# Sheet1.net
KiCad netlist of a schematic drawn in Altium Designer
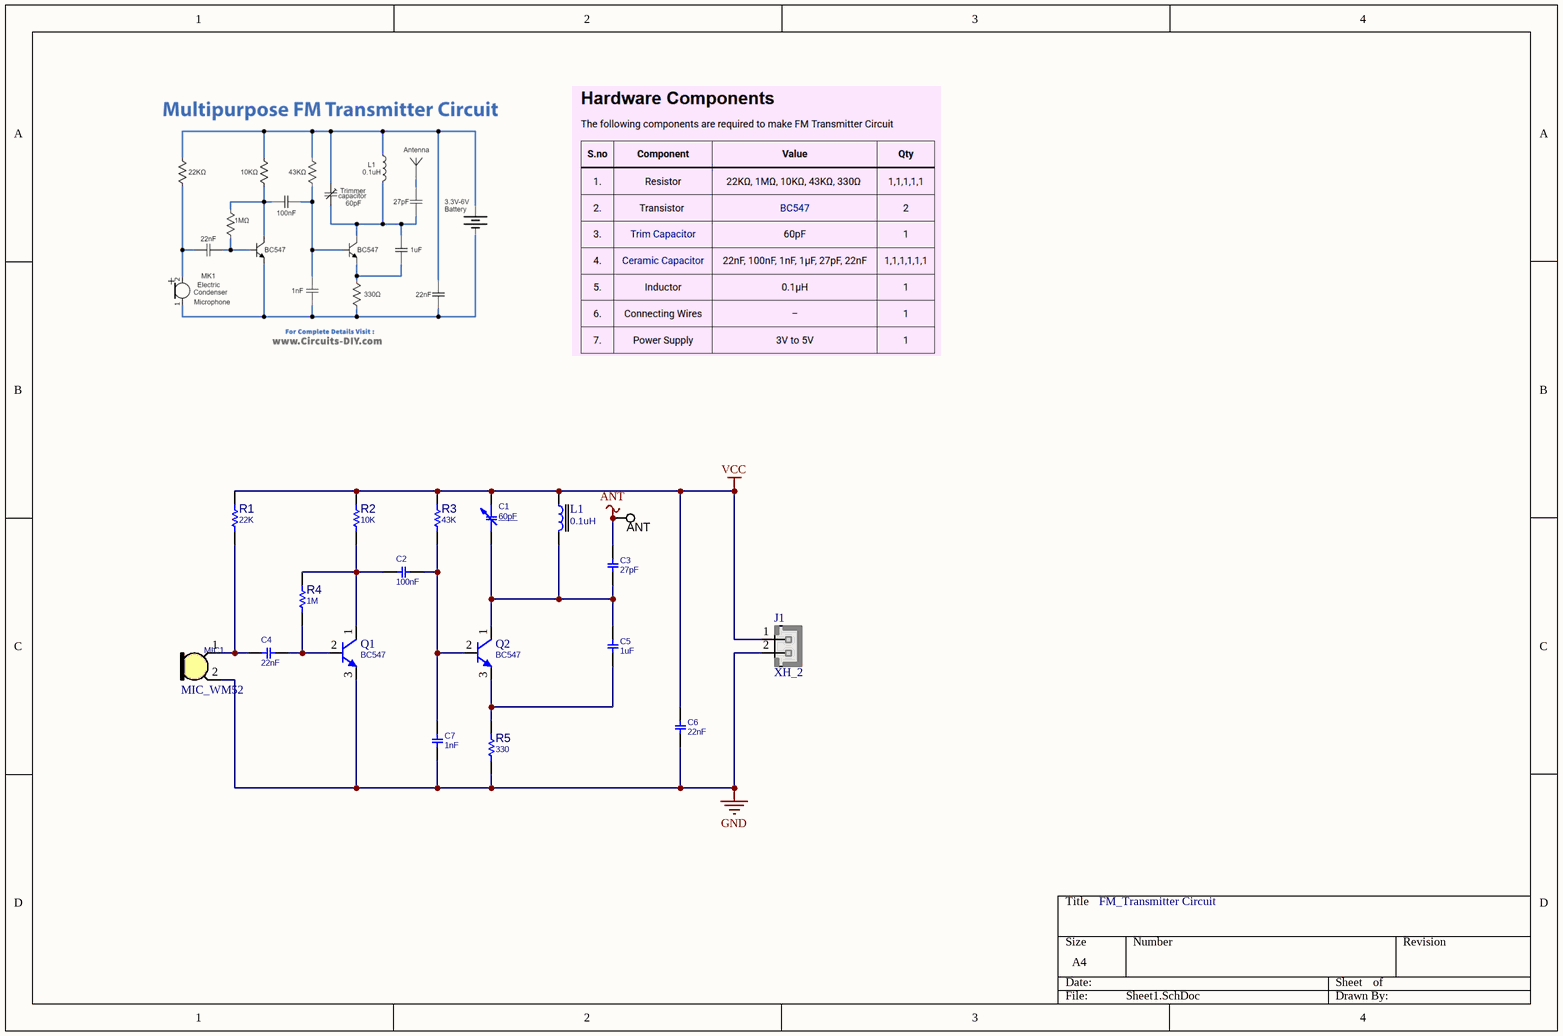
[diagram p0: Sheet1.SchDoc]

(export (version "E")
  (design (tool "Eeschema 10.0.6"))
  (components
    (comp (ref "ANT")
      (value "TESTPOINT_PROBE")
      (footprint "TP80D50")
      (description "TEST POINT")
      (fields (field (name "MANF") "MANF") (field (name "MANF_P#") "MANF_P#"))
      (libsource (lib "test-tp_jumper") (part "TESTPOINT_PROBE"))
    )
    (comp (ref "C1")
      (value "60pF")
      (footprint "CTRM_6X6")
      (description "CAP, THD, TRIMMER")
      (fields (field (name "MANF_P#") "MANF_PART#") (field (name "MANF") "MANF"))
      (libsource (lib "passive_thd") (part "CAP_THD_TRIMMER"))
    )
    (comp (ref "C2")
      (value "100nF")
      (footprint "C_CER_D5")
      (description "CAP, THD, CER MULTI LAYER,")
      (fields (field (name "MANF_P#") "MANF_PART#") (field (name "MANF") "MANF"))
      (libsource (lib "passive_thd") (part "CAP_THD_CER"))
    )
    (comp (ref "C3")
      (value "27pF")
      (footprint "C_CER_D5")
      (description "CAP, THD, CER MULTI LAYER,")
      (fields (field (name "MANF_P#") "MANF_PART#") (field (name "MANF") "MANF"))
      (libsource (lib "passive_thd") (part "CAP_THD_CER"))
    )
    (comp (ref "C4")
      (value "22nF")
      (footprint "C_CER_D5")
      (description "CAP, THD, CER MULTI LAYER,")
      (fields (field (name "MANF_P#") "MANF_PART#") (field (name "MANF") "MANF"))
      (libsource (lib "passive_thd") (part "CAP_THD_CER"))
    )
    (comp (ref "C5")
      (value "1uF")
      (footprint "C_CER_D5")
      (description "CAP, THD, CER MULTI LAYER,")
      (fields (field (name "MANF_P#") "MANF_PART#") (field (name "MANF") "MANF"))
      (libsource (lib "passive_thd") (part "CAP_THD_CER"))
    )
    (comp (ref "C6")
      (value "22nF")
      (footprint "C_CER_D5")
      (description "CAP, THD, CER MULTI LAYER,")
      (fields (field (name "MANF_P#") "MANF_PART#") (field (name "MANF") "MANF"))
      (libsource (lib "passive_thd") (part "CAP_THD_CER"))
    )
    (comp (ref "C7")
      (value "1nF")
      (footprint "C_CER_D5")
      (description "CAP, THD, CER MULTI LAYER,")
      (fields (field (name "MANF_P#") "MANF_PART#") (field (name "MANF") "MANF"))
      (libsource (lib "passive_thd") (part "CAP_THD_CER"))
    )
    (comp (ref "J1")
      (value "XH_2")
      (footprint "XH_2")
      (description "PW10-x-M, JST-BxB-XH-A pitch: 2.5mm, 3A/250v")
      (fields (field (name "MANF") "JST") (field (name "MANF_P#") "B2B-XH-A"))
      (libsource (lib "conn_wire2board") (part "XH_2"))
    )
    (comp (ref "L1")
      (value "0.1uH")
      (footprint "LT_AX025")
      (description "INDUCTOR, THD")
      (fields (field (name "L1") "0.1uH"))
      (libsource (lib "passive_thd") (part "IND_THD"))
    )
    (comp (ref "MIC1")
      (value "MIC_WM52")
      (footprint "MIC_C6")
      (description "MICROPHONE OMNI")
      (fields (field (name "MANF_P#") "WM52BM"))
      (libsource (lib "audio_mic_spk") (part "MIC_WM-52"))
    )
    (comp (ref "Q1")
      (value "BC547")
      (footprint "TO92_3")
      (description "BJT, NPN, 45v, 0.1A, THD, TO92")
      (fields (field (name "MANF") "FAIRCHILD"))
      (libsource (lib "transistor_bjt") (part "NPN_BC547_TO92"))
    )
    (comp (ref "Q2")
      (value "BC547")
      (footprint "TO92_3")
      (description "BJT, NPN, 45v, 0.1A, THD, TO92")
      (fields (field (name "MANF") "FAIRCHILD"))
      (libsource (lib "transistor_bjt") (part "NPN_BC547_TO92"))
    )
    (comp (ref "R1")
      (value "22K")
      (footprint "R025W_AX04")
      (description "RESISTOR, THD")
      (fields (field (name "MANF_P#") "RK73H1ETTP4701F") (field (name "MANF") "KOA SPEER"))
      (libsource (lib "passive_thd") (part "RES_THD"))
    )
    (comp (ref "R2")
      (value "10K")
      (footprint "R025W_AX04")
      (description "RESISTOR, THD")
      (fields (field (name "MANF_P#") "RK73H1ETTP4701F") (field (name "MANF") "KOA SPEER"))
      (libsource (lib "passive_thd") (part "RES_THD"))
    )
    (comp (ref "R3")
      (value "43K")
      (footprint "R025W_AX04")
      (description "RESISTOR, THD")
      (fields (field (name "MANF_P#") "RK73H1ETTP4701F") (field (name "MANF") "KOA SPEER"))
      (libsource (lib "passive_thd") (part "RES_THD"))
    )
    (comp (ref "R4")
      (value "1M")
      (footprint "R025W_AX04")
      (description "RESISTOR, THD")
      (fields (field (name "MANF_P#") "RK73H1ETTP4701F") (field (name "MANF") "KOA SPEER"))
      (libsource (lib "passive_thd") (part "RES_THD"))
    )
    (comp (ref "R5")
      (value "330")
      (footprint "R025W_AX04")
      (description "RESISTOR, THD")
      (fields (field (name "MANF_P#") "RK73H1ETTP4701F") (field (name "MANF") "KOA SPEER"))
      (libsource (lib "passive_thd") (part "RES_THD"))
    )
  )
  (nets
    (net (code "1") (name "ANT") (class "Default")
      (node (ref "ANT") (pin "1") (pinfunction "1_1") (pintype "passive"))
      (node (ref "C3") (pin "2") (pinfunction "2_2") (pintype "passive"))
    )
    (net (code "2") (name "GND") (class "Default")
      (node (ref "C6") (pin "1") (pinfunction "1_1") (pintype "passive"))
      (node (ref "C7") (pin "1") (pinfunction "1_1") (pintype "passive"))
      (node (ref "J1") (pin "2") (pinfunction "2_2") (pintype "passive"))
      (node (ref "MIC1") (pin "2") (pinfunction "GND_2") (pintype "passive"))
      (node (ref "Q1") (pin "3") (pinfunction "E_3") (pintype "passive"))
      (node (ref "R5") (pin "1") (pinfunction "1_1") (pintype "passive"))
    )
    (net (code "3") (name "Net-(MIC1-OUT)") (class "Default")
      (node (ref "C4") (pin "1") (pinfunction "1_1") (pintype "passive"))
      (node (ref "MIC1") (pin "1") (pinfunction "OUT_1") (pintype "passive"))
      (node (ref "R1") (pin "1") (pinfunction "1_1") (pintype "passive"))
    )
    (net (code "4") (name "Net-(Q1-B)") (class "Default")
      (node (ref "C4") (pin "2") (pinfunction "2_2") (pintype "passive"))
      (node (ref "Q1") (pin "2") (pinfunction "B_2") (pintype "passive"))
      (node (ref "R4") (pin "1") (pinfunction "1_1") (pintype "passive"))
    )
    (net (code "5") (name "Net-(Q1-C)") (class "Default")
      (node (ref "C2") (pin "1") (pinfunction "1_1") (pintype "passive"))
      (node (ref "Q1") (pin "1") (pinfunction "C_1") (pintype "passive"))
      (node (ref "R2") (pin "1") (pinfunction "1_1") (pintype "passive"))
      (node (ref "R4") (pin "2") (pinfunction "2_2") (pintype "passive"))
    )
    (net (code "6") (name "Net-(Q2-B)") (class "Default")
      (node (ref "C2") (pin "2") (pinfunction "2_2") (pintype "passive"))
      (node (ref "C7") (pin "2") (pinfunction "2_2") (pintype "passive"))
      (node (ref "Q2") (pin "2") (pinfunction "B_2") (pintype "passive"))
      (node (ref "R3") (pin "1") (pinfunction "1_1") (pintype "passive"))
    )
    (net (code "7") (name "Net-(Q2-C)") (class "Default")
      (node (ref "C1") (pin "1") (pinfunction "1_1") (pintype "passive"))
      (node (ref "C3") (pin "1") (pinfunction "1_1") (pintype "passive"))
      (node (ref "C5") (pin "2") (pinfunction "2_2") (pintype "passive"))
      (node (ref "L1") (pin "2") (pinfunction "2_2") (pintype "passive"))
      (node (ref "Q2") (pin "1") (pinfunction "C_1") (pintype "passive"))
    )
    (net (code "8") (name "Net-(Q2-E)") (class "Default")
      (node (ref "C5") (pin "1") (pinfunction "1_1") (pintype "passive"))
      (node (ref "Q2") (pin "3") (pinfunction "E_3") (pintype "passive"))
      (node (ref "R5") (pin "2") (pinfunction "2_2") (pintype "passive"))
    )
    (net (code "9") (name "VCC") (class "Default")
      (node (ref "C1") (pin "2") (pinfunction "2_2") (pintype "passive"))
      (node (ref "C6") (pin "2") (pinfunction "2_2") (pintype "passive"))
      (node (ref "J1") (pin "1") (pinfunction "1_1") (pintype "passive"))
      (node (ref "L1") (pin "1") (pinfunction "1_1") (pintype "passive"))
      (node (ref "R1") (pin "2") (pinfunction "2_2") (pintype "passive"))
      (node (ref "R2") (pin "2") (pinfunction "2_2") (pintype "passive"))
      (node (ref "R3") (pin "2") (pinfunction "2_2") (pintype "passive"))
    )
  )
)
